# AK4430_1.net
KiCad netlist of a schematic drawn in Altium Designer
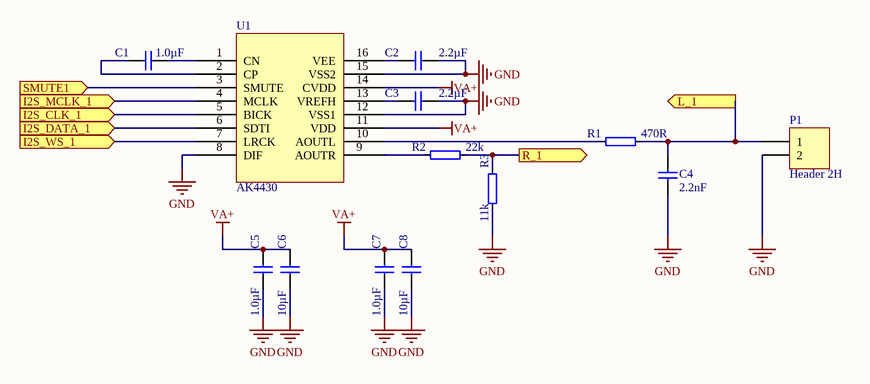
[diagram p0: AK4430_1.SchDoc]

(export (version "E")
  (design (tool "Eeschema 10.0.6"))
  (components
    (comp (ref "C1")
      (value "1.0µF")
      (footprint "0603s")
      (description "Chip Cap 0603")
      (fields (field (name "PART NUMBER") "C0603-1µ0") (field (name "PUBLISHER") "Nordic Semiconductor"))
      (libsource (lib "Nordic Passive DB") (part "CAP"))
    )
    (comp (ref "C2")
      (value "2.2µF")
      (footprint "0603s")
      (description "Chip Cap 0603")
      (fields (field (name "PART NUMBER") "C0603-2µ2") (field (name "PUBLISHER") "Nordic Semiconductor"))
      (libsource (lib "Nordic Passive DB") (part "CAP"))
    )
    (comp (ref "C3")
      (value "2.2µF")
      (footprint "0603s")
      (description "Chip Cap 0603")
      (fields (field (name "PART NUMBER") "C0603-2µ2") (field (name "PUBLISHER") "Nordic Semiconductor"))
      (libsource (lib "Nordic Passive DB") (part "CAP"))
    )
    (comp (ref "C4")
      (value "2.2nF")
      (footprint "0402s")
      (description "Chip Cap 0402")
      (fields (field (name "PART NUMBER") "C0402-2n2") (field (name "PUBLISHER") "Nordic Semiconductor"))
      (libsource (lib "Nordic Passive DB") (part "CAP"))
    )
    (comp (ref "C5")
      (value "1.0µF")
      (footprint "0603s")
      (description "Chip Cap 0603")
      (fields (field (name "PART NUMBER") "C0603-1µ0") (field (name "PUBLISHER") "Nordic Semiconductor"))
      (libsource (lib "Nordic Passive DB") (part "CAP"))
    )
    (comp (ref "C6")
      (value "10µF")
      (footprint "0805")
      (description "Chip Cap 0805")
      (fields (field (name "PART NUMBER") "C0805-10µ") (field (name "PUBLISHER") "Nordic Semiconductor"))
      (libsource (lib "Nordic Passive DB") (part "CAP"))
    )
    (comp (ref "C7")
      (value "1.0µF")
      (footprint "0603s")
      (description "Chip Cap 0603")
      (fields (field (name "PART NUMBER") "C0603-1µ0") (field (name "PUBLISHER") "Nordic Semiconductor"))
      (libsource (lib "Nordic Passive DB") (part "CAP"))
    )
    (comp (ref "C8")
      (value "10µF")
      (footprint "0805")
      (description "Chip Cap 0805")
      (fields (field (name "PART NUMBER") "C0805-10µ") (field (name "PUBLISHER") "Nordic Semiconductor"))
      (libsource (lib "Nordic Passive DB") (part "CAP"))
    )
    (comp (ref "P1")
      (value "Header 2H")
      (footprint "RCA")
      (description "Header, 2-Pin, Right Angle")
      (fields (field (name "PUBLISHER") "Altium Limited"))
      (libsource (lib "Miscellaneous Connectors") (part "Header 2H"))
    )
    (comp (ref "R1")
      (value "470R")
      (footprint "0402s")
      (description "Chip Res 0402")
      (fields (field (name "PART NUMBER") "R0402-470") (field (name "PUBLISHER") "Nordic Semiconductor"))
      (libsource (lib "Nordic Passive DB") (part "RES_1"))
    )
    (comp (ref "R2")
      (value "22k")
      (footprint "0402s")
      (description "Chip Res 0402")
      (fields (field (name "PART NUMBER") "R0402-22k") (field (name "PUBLISHER") "Nordic Semiconductor"))
      (libsource (lib "Nordic Passive DB") (part "RES_1"))
    )
    (comp (ref "R3")
      (value "11k")
      (footprint "0402s")
      (description "Chip Res 0402")
      (fields (field (name "PART NUMBER") "R0402-10k") (field (name "PUBLISHER") "Nordic Semiconductor"))
      (libsource (lib "Nordic Passive DB") (part "RES_1"))
    )
    (comp (ref "U1")
      (value "AK4430")
      (footprint "TSOP65P640X110-16N")
      (libsource (lib "nRF2460") (part "AK4430"))
    )
  )
  (nets
    (net (code "1") (name "/I2S_CLK_1") (class "Default")
      (node (ref "U1") (pin "5") (pinfunction "BICK_5") (pintype "passive"))
    )
    (net (code "2") (name "/I2S_DATA_1") (class "Default")
      (node (ref "U1") (pin "6") (pinfunction "SDTI_6") (pintype "passive"))
    )
    (net (code "3") (name "/I2S_MCLK_1") (class "Default")
      (node (ref "U1") (pin "4") (pinfunction "MCLK_4") (pintype "passive"))
    )
    (net (code "4") (name "/I2S_WS_1") (class "Default")
      (node (ref "U1") (pin "7") (pinfunction "LRCK_7") (pintype "passive"))
    )
    (net (code "5") (name "/L_1") (class "Default")
      (node (ref "C4") (pin "2") (pinfunction "2_2") (pintype "passive"))
      (node (ref "P1") (pin "1") (pinfunction "1_1") (pintype "passive"))
      (node (ref "R1") (pin "2") (pinfunction "2_2") (pintype "passive"))
    )
    (net (code "6") (name "/R_1") (class "Default")
      (node (ref "R2") (pin "2") (pinfunction "2_2") (pintype "passive"))
      (node (ref "R3") (pin "2") (pinfunction "2_2") (pintype "passive"))
    )
    (net (code "7") (name "/SMUTE1") (class "Default")
      (node (ref "U1") (pin "3") (pinfunction "SMUTE_3") (pintype "passive"))
    )
    (net (code "8") (name "GND") (class "Default")
      (node (ref "C2") (pin "2") (pinfunction "2_2") (pintype "passive"))
      (node (ref "C3") (pin "2") (pinfunction "2_2") (pintype "passive"))
      (node (ref "C4") (pin "1") (pinfunction "1_1") (pintype "passive"))
      (node (ref "C5") (pin "1") (pinfunction "1_1") (pintype "passive"))
      (node (ref "C6") (pin "1") (pinfunction "1_1") (pintype "passive"))
      (node (ref "C7") (pin "1") (pinfunction "1_1") (pintype "passive"))
      (node (ref "C8") (pin "1") (pinfunction "1_1") (pintype "passive"))
      (node (ref "P1") (pin "2") (pinfunction "2_2") (pintype "passive"))
      (node (ref "R3") (pin "1") (pinfunction "1_1") (pintype "passive"))
      (node (ref "U1") (pin "12") (pinfunction "VSS1_12") (pintype "passive"))
      (node (ref "U1") (pin "15") (pinfunction "VSS2_15") (pintype "passive"))
      (node (ref "U1") (pin "8") (pinfunction "DIF_8") (pintype "passive"))
    )
    (net (code "9") (name "Net-(U1-AOUTL)") (class "Default")
      (node (ref "R1") (pin "1") (pinfunction "1_1") (pintype "passive"))
      (node (ref "U1") (pin "10") (pinfunction "AOUTL_10") (pintype "passive"))
    )
    (net (code "10") (name "Net-(U1-AOUTR)") (class "Default")
      (node (ref "R2") (pin "1") (pinfunction "1_1") (pintype "passive"))
      (node (ref "U1") (pin "9") (pinfunction "AOUTR_9") (pintype "passive"))
    )
    (net (code "11") (name "Net-(U1-CN)") (class "Default")
      (node (ref "C1") (pin "2") (pinfunction "2_2") (pintype "passive"))
      (node (ref "U1") (pin "1") (pinfunction "CN_1") (pintype "passive"))
    )
    (net (code "12") (name "Net-(U1-CP)") (class "Default")
      (node (ref "C1") (pin "1") (pinfunction "1_1") (pintype "passive"))
      (node (ref "U1") (pin "2") (pinfunction "CP_2") (pintype "passive"))
    )
    (net (code "13") (name "Net-(U1-VEE)") (class "Default")
      (node (ref "C2") (pin "1") (pinfunction "1_1") (pintype "passive"))
      (node (ref "U1") (pin "16") (pinfunction "VEE_16") (pintype "passive"))
    )
    (net (code "14") (name "Net-(U1-VREFH)") (class "Default")
      (node (ref "C3") (pin "1") (pinfunction "1_1") (pintype "passive"))
      (node (ref "U1") (pin "13") (pinfunction "VREFH_13") (pintype "passive"))
    )
    (net (code "15") (name "VA+") (class "Default")
      (node (ref "C5") (pin "2") (pinfunction "2_2") (pintype "passive"))
      (node (ref "C6") (pin "2") (pinfunction "2_2") (pintype "passive"))
      (node (ref "C7") (pin "2") (pinfunction "2_2") (pintype "passive"))
      (node (ref "C8") (pin "2") (pinfunction "2_2") (pintype "passive"))
      (node (ref "U1") (pin "11") (pinfunction "VDD_11") (pintype "passive"))
      (node (ref "U1") (pin "14") (pinfunction "CVDD_14") (pintype "passive"))
    )
  )
)
